# FLC100_remote_v1_2.net
KiCad netlist of a schematic drawn in EAGLE
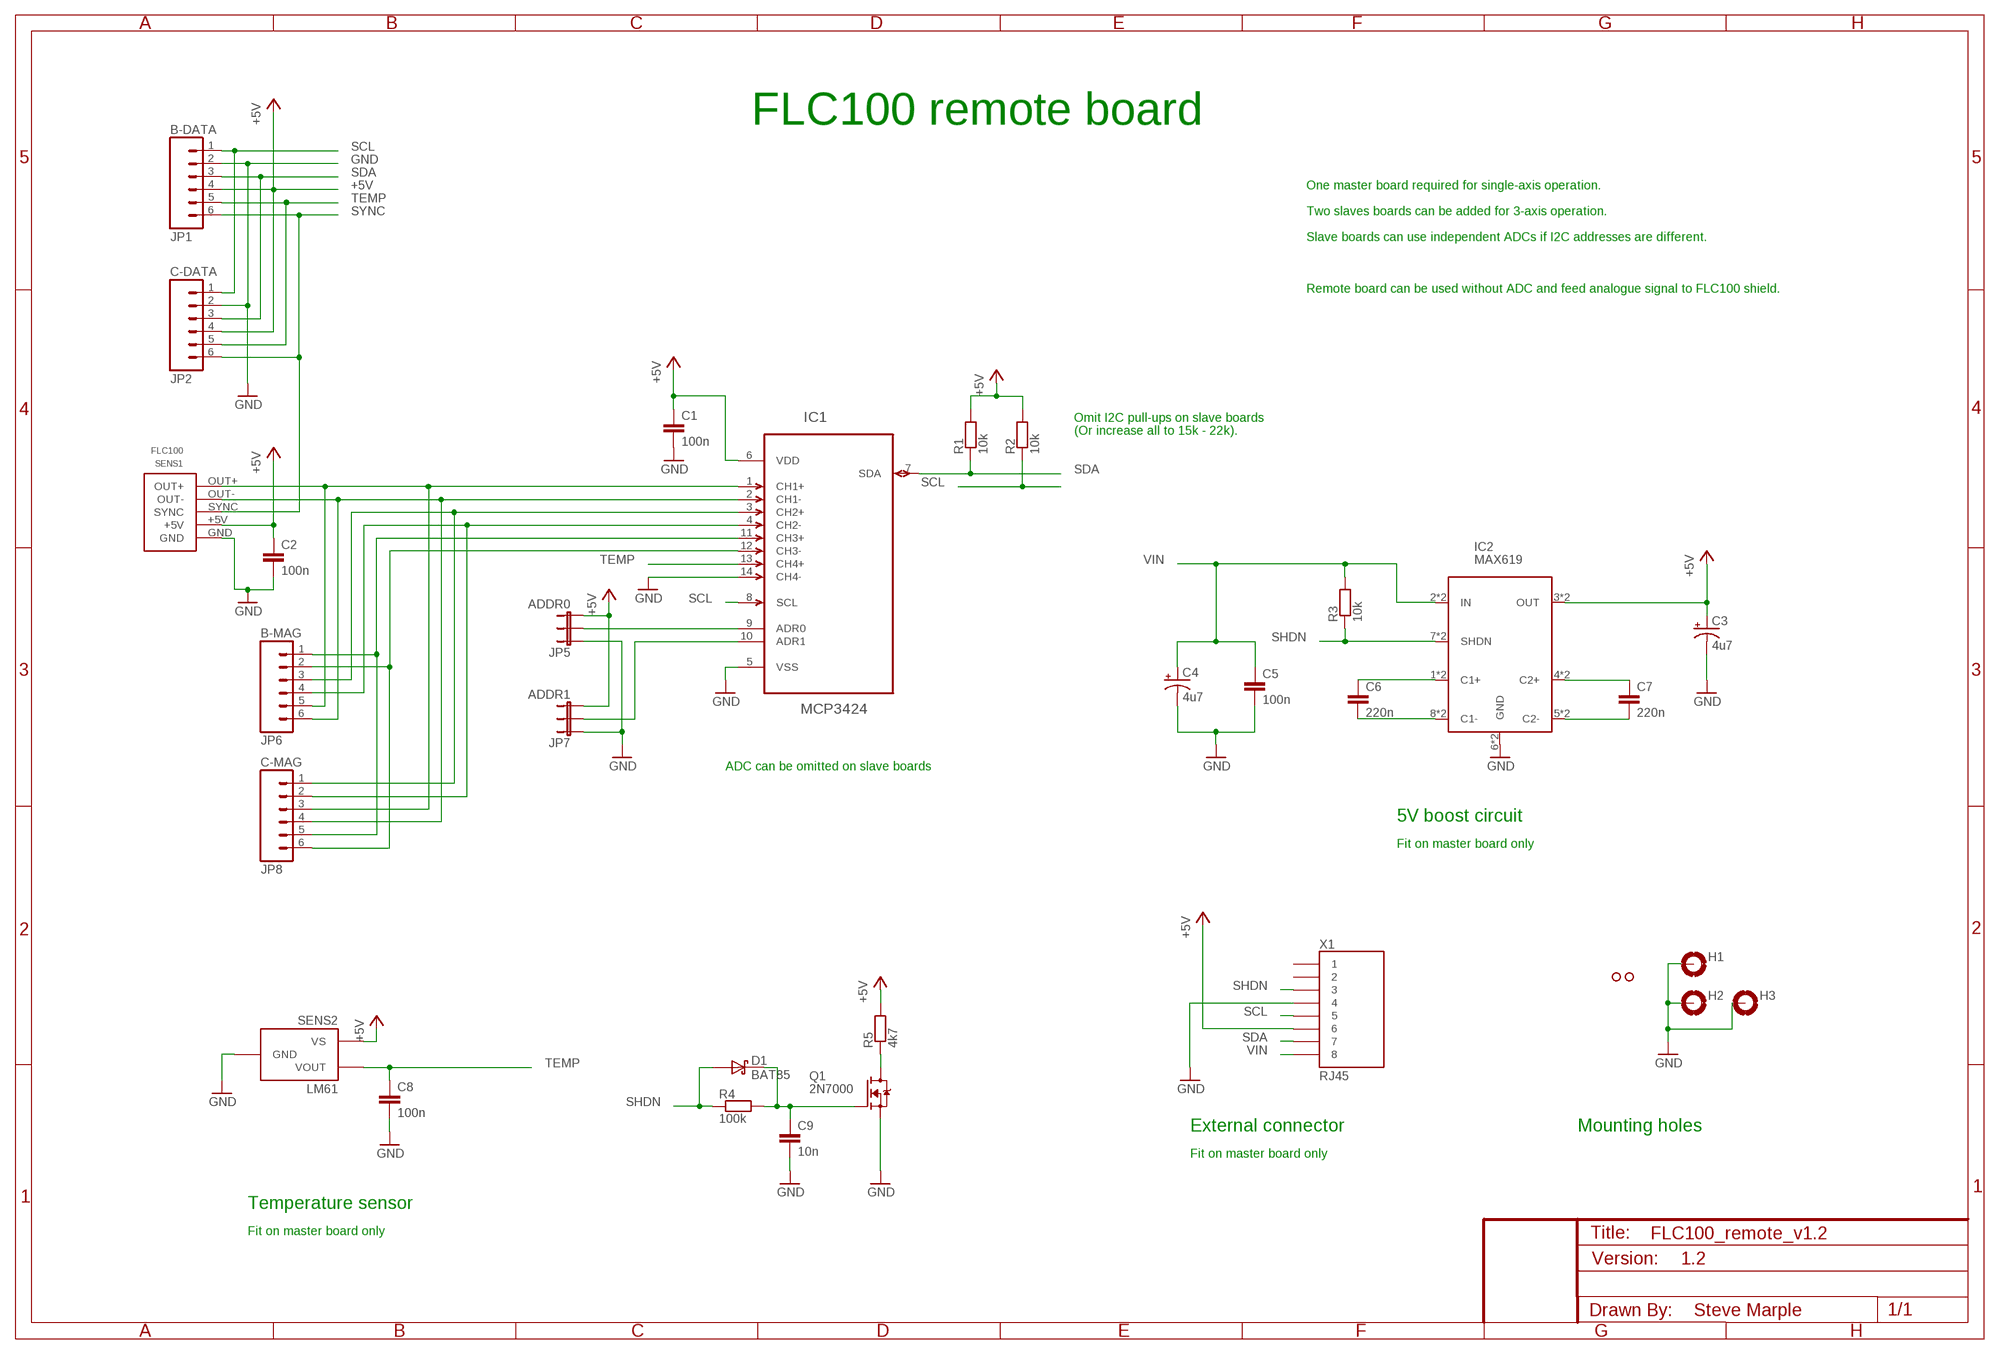
[diagram p0: schematic, sheet 1]

(export (version "E")
  (design (tool "Eeschema 10.0.6"))
  (components
    (comp (ref "C1")
      (value "100n")
      (footprint "eagle-import:CAP-PTH-SMALL")
      (libsource (lib "eagle-import") (part "CAPPTH"))
    )
    (comp (ref "C2")
      (value "100n")
      (footprint "eagle-import:CAP-PTH-SMALL")
      (libsource (lib "eagle-import") (part "CAPPTH"))
    )
    (comp (ref "C3")
      (value "4u7")
      (footprint "eagle-import:CPOL-RADIAL-10UF-25V")
      (libsource (lib "eagle-import") (part "CAP_POLPTH2"))
    )
    (comp (ref "C4")
      (value "4u7")
      (footprint "eagle-import:CPOL-RADIAL-10UF-25V")
      (libsource (lib "eagle-import") (part "CAP_POLPTH2"))
    )
    (comp (ref "C5")
      (value "100n")
      (footprint "eagle-import:CAP-PTH-SMALL")
      (libsource (lib "eagle-import") (part "CAPPTH"))
    )
    (comp (ref "C6")
      (value "220n")
      (footprint "eagle-import:CAP-PTH-5MM")
      (libsource (lib "eagle-import") (part "CAPPTH1"))
    )
    (comp (ref "C7")
      (value "220n")
      (footprint "eagle-import:CAP-PTH-5MM")
      (libsource (lib "eagle-import") (part "CAPPTH1"))
    )
    (comp (ref "C8")
      (value "100n")
      (footprint "eagle-import:CAP-PTH-SMALL")
      (libsource (lib "eagle-import") (part "CAPPTH"))
    )
    (comp (ref "C9")
      (value "10n")
      (footprint "eagle-import:CAP-PTH-SMALL")
      (libsource (lib "eagle-import") (part "CAPPTH"))
    )
    (comp (ref "D1")
      (value "BAT85")
      (footprint "eagle-import:DIODE-TH-0.4")
      (libsource (lib "eagle-import") (part "DIODE-SCHOTTKY"))
    )
    (comp (ref "H1")
      (value "MOUNT-PAD-ROUND3.0")
      (footprint "eagle-import:3,0-PAD")
      (libsource (lib "eagle-import") (part "MOUNT-PAD-ROUND3.0"))
    )
    (comp (ref "H2")
      (value "MOUNT-PAD-ROUND3.0")
      (footprint "eagle-import:3,0-PAD")
      (libsource (lib "eagle-import") (part "MOUNT-PAD-ROUND3.0"))
    )
    (comp (ref "H3")
      (value "MOUNT-PAD-ROUND3.0")
      (footprint "eagle-import:3,0-PAD")
      (libsource (lib "eagle-import") (part "MOUNT-PAD-ROUND3.0"))
    )
    (comp (ref "IC1")
      (value "MCP3424")
      (footprint "eagle-import:SO14")
      (libsource (lib "eagle-import") (part "MCP3424-E/SLSO14"))
    )
    (comp (ref "IC2")
      (value "MAX619")
      (footprint "eagle-import:DIL08-SOIC8")
      (libsource (lib "eagle-import") (part "MAX619DIL08/SOIC8"))
    )
    (comp (ref "JP1")
      (value "B-DATA")
      (footprint "eagle-import:1X06_FEMALE")
      (libsource (lib "eagle-import") (part "M06FEMALE"))
    )
    (comp (ref "JP2")
      (value "C-DATA")
      (footprint "eagle-import:1X06_FEMALE")
      (libsource (lib "eagle-import") (part "M06FEMALE"))
    )
    (comp (ref "JP5")
      (value "ADDR0")
      (footprint "eagle-import:1X03")
      (libsource (lib "eagle-import") (part "JUMPER-3PTH"))
    )
    (comp (ref "JP6")
      (value "B-MAG")
      (footprint "eagle-import:1X06_FEMALE")
      (libsource (lib "eagle-import") (part "M06FEMALE"))
    )
    (comp (ref "JP7")
      (value "ADDR1")
      (footprint "eagle-import:1X03")
      (libsource (lib "eagle-import") (part "JUMPER-3PTH"))
    )
    (comp (ref "JP8")
      (value "C-MAG")
      (footprint "eagle-import:1X06_FEMALE")
      (libsource (lib "eagle-import") (part "M06FEMALE"))
    )
    (comp (ref "Q1")
      (value "2N7000")
      (footprint "eagle-import:TO-92")
      (libsource (lib "eagle-import") (part "2N7000"))
    )
    (comp (ref "R1")
      (value "10k")
      (footprint "eagle-import:RES-AXIAL-0.4")
      (libsource (lib "eagle-import") (part "RESISTOR"))
    )
    (comp (ref "R2")
      (value "10k")
      (footprint "eagle-import:RES-AXIAL-0.4")
      (libsource (lib "eagle-import") (part "RESISTOR"))
    )
    (comp (ref "R3")
      (value "10k")
      (footprint "eagle-import:RES-AXIAL-0.4")
      (libsource (lib "eagle-import") (part "RESISTOR"))
    )
    (comp (ref "R4")
      (value "100k")
      (footprint "eagle-import:RES-AXIAL-0.4")
      (libsource (lib "eagle-import") (part "RESISTOR"))
    )
    (comp (ref "R5")
      (value "4k7")
      (footprint "eagle-import:RES-AXIAL-0.4")
      (libsource (lib "eagle-import") (part "RESISTOR"))
    )
    (comp (ref "SENS1")
      (value "FLC100")
      (footprint "eagle-import:FLC100")
      (libsource (lib "eagle-import") (part "FLC100"))
    )
    (comp (ref "SENS2")
      (value "LM61")
      (footprint "eagle-import:TO-92")
      (libsource (lib "eagle-import") (part "LM61"))
    )
    (comp (ref "U$1")
      (value "PAD")
      (footprint "eagle-import:PAD")
      (libsource (lib "eagle-import") (part "PAD"))
    )
    (comp (ref "U$2")
      (value "PAD")
      (footprint "eagle-import:PAD")
      (libsource (lib "eagle-import") (part "PAD"))
    )
    (comp (ref "X1")
      (value "RJ45")
      (footprint "eagle-import:RJ45-8")
      (libsource (lib "eagle-import") (part "RJ45-8PTH"))
    )
  )
  (nets
    (net (code "1") (name "+5V") (class "Default")
      (node (ref "C1") (pin "1") (pinfunction "1_1") (pintype "passive"))
      (node (ref "C2") (pin "1") (pinfunction "1_1") (pintype "passive"))
      (node (ref "C3") (pin "1") (pinfunction "+_1") (pintype "passive"))
      (node (ref "IC1") (pin "6") (pinfunction "VDD_6") (pintype "power_in"))
      (node (ref "IC2") (pin "3") (pinfunction "OUT_3") (pintype "power_in"))
      (node (ref "IC2") (pin "3@1") (pinfunction "OUT_3@1") (pintype "power_in"))
      (node (ref "JP1") (pin "4") (pinfunction "4_4") (pintype "passive"))
      (node (ref "JP2") (pin "4") (pinfunction "4_4") (pintype "passive"))
      (node (ref "JP5") (pin "3") (pinfunction "3_3") (pintype "passive"))
      (node (ref "JP7") (pin "3") (pinfunction "3_3") (pintype "passive"))
      (node (ref "R1") (pin "P$2") (pinfunction "2_P$2") (pintype "passive"))
      (node (ref "R2") (pin "P$2") (pinfunction "2_P$2") (pintype "passive"))
      (node (ref "R5") (pin "P$2") (pinfunction "2_P$2") (pintype "passive"))
      (node (ref "SENS1") (pin "+5V") (pinfunction "+5V_+5V") (pintype "power_in"))
      (node (ref "SENS2") (pin "1") (pinfunction "VS_1") (pintype "bidirectional"))
      (node (ref "X1") (pin "6") (pinfunction "6_6") (pintype "bidirectional"))
    )
    (net (code "2") (name "/SCL") (class "Default")
      (node (ref "IC1") (pin "8") (pinfunction "SCL_8") (pintype "input"))
      (node (ref "JP1") (pin "1") (pinfunction "1_1") (pintype "passive"))
      (node (ref "JP2") (pin "1") (pinfunction "1_1") (pintype "passive"))
      (node (ref "R2") (pin "P$1") (pinfunction "1_P$1") (pintype "passive"))
      (node (ref "X1") (pin "5") (pinfunction "5_5") (pintype "bidirectional"))
    )
    (net (code "3") (name "/SDA") (class "Default")
      (node (ref "IC1") (pin "7") (pinfunction "SDA_7") (pintype "bidirectional"))
      (node (ref "JP1") (pin "3") (pinfunction "3_3") (pintype "passive"))
      (node (ref "JP2") (pin "3") (pinfunction "3_3") (pintype "passive"))
      (node (ref "R1") (pin "P$1") (pinfunction "1_P$1") (pintype "passive"))
      (node (ref "X1") (pin "7") (pinfunction "7_7") (pintype "bidirectional"))
    )
    (net (code "4") (name "/SHDN") (class "Default")
      (node (ref "D1") (pin "A") (pinfunction "A_A") (pintype "passive"))
      (node (ref "IC2") (pin "7") (pinfunction "SHDN_7") (pintype "input"))
      (node (ref "IC2") (pin "7@1") (pinfunction "SHDN_7@1") (pintype "input"))
      (node (ref "R3") (pin "P$1") (pinfunction "1_P$1") (pintype "passive"))
      (node (ref "R4") (pin "P$1") (pinfunction "1_P$1") (pintype "passive"))
      (node (ref "X1") (pin "3") (pinfunction "3_3") (pintype "bidirectional"))
    )
    (net (code "5") (name "/SYNC") (class "Default")
      (node (ref "JP1") (pin "6") (pinfunction "6_6") (pintype "passive"))
      (node (ref "JP2") (pin "6") (pinfunction "6_6") (pintype "passive"))
      (node (ref "SENS1") (pin "SYNC") (pinfunction "SYNC_SYNC") (pintype "bidirectional"))
    )
    (net (code "6") (name "/TEMP") (class "Default")
      (node (ref "C8") (pin "1") (pinfunction "1_1") (pintype "passive"))
      (node (ref "IC1") (pin "13") (pinfunction "CH4+_13") (pintype "input"))
      (node (ref "JP1") (pin "5") (pinfunction "5_5") (pintype "passive"))
      (node (ref "JP2") (pin "5") (pinfunction "5_5") (pintype "passive"))
      (node (ref "SENS2") (pin "2") (pinfunction "VOUT_2") (pintype "bidirectional"))
    )
    (net (code "7") (name "/VIN") (class "Default")
      (node (ref "C4") (pin "1") (pinfunction "+_1") (pintype "passive"))
      (node (ref "C5") (pin "1") (pinfunction "1_1") (pintype "passive"))
      (node (ref "IC2") (pin "2") (pinfunction "IN_2") (pintype "power_in"))
      (node (ref "IC2") (pin "2@1") (pinfunction "IN_2@1") (pintype "power_in"))
      (node (ref "R3") (pin "P$2") (pinfunction "2_P$2") (pintype "passive"))
      (node (ref "X1") (pin "8") (pinfunction "8_8") (pintype "bidirectional"))
    )
    (net (code "8") (name "GND") (class "Default")
      (node (ref "C1") (pin "2") (pinfunction "2_2") (pintype "passive"))
      (node (ref "C2") (pin "2") (pinfunction "2_2") (pintype "passive"))
      (node (ref "C3") (pin "2") (pinfunction "-_2") (pintype "passive"))
      (node (ref "C4") (pin "2") (pinfunction "-_2") (pintype "passive"))
      (node (ref "C5") (pin "2") (pinfunction "2_2") (pintype "passive"))
      (node (ref "C8") (pin "2") (pinfunction "2_2") (pintype "passive"))
      (node (ref "C9") (pin "2") (pinfunction "2_2") (pintype "passive"))
      (node (ref "H1") (pin "B3,0") (pinfunction "MOUNT_B3,0") (pintype "passive"))
      (node (ref "H2") (pin "B3,0") (pinfunction "MOUNT_B3,0") (pintype "passive"))
      (node (ref "H3") (pin "B3,0") (pinfunction "MOUNT_B3,0") (pintype "passive"))
      (node (ref "IC1") (pin "14") (pinfunction "CH4-_14") (pintype "input"))
      (node (ref "IC1") (pin "5") (pinfunction "VSS_5") (pintype "power_in"))
      (node (ref "IC2") (pin "6") (pinfunction "GND_6") (pintype "power_in"))
      (node (ref "IC2") (pin "6@1") (pinfunction "GND_6@1") (pintype "power_in"))
      (node (ref "JP1") (pin "2") (pinfunction "2_2") (pintype "passive"))
      (node (ref "JP2") (pin "2") (pinfunction "2_2") (pintype "passive"))
      (node (ref "JP5") (pin "1") (pinfunction "1_1") (pintype "passive"))
      (node (ref "JP7") (pin "1") (pinfunction "1_1") (pintype "passive"))
      (node (ref "Q1") (pin "1") (pinfunction "S_1") (pintype "passive"))
      (node (ref "SENS1") (pin "GND") (pinfunction "GND_GND") (pintype "power_in"))
      (node (ref "SENS2") (pin "3") (pinfunction "GND_3") (pintype "bidirectional"))
      (node (ref "X1") (pin "4") (pinfunction "4_4") (pintype "bidirectional"))
    )
    (net (code "9") (name "Net-(C6-Pad1)") (class "Default")
      (node (ref "C6") (pin "1") (pinfunction "1_1") (pintype "passive"))
      (node (ref "IC2") (pin "1") (pinfunction "C1+_1") (pintype "bidirectional"))
      (node (ref "IC2") (pin "1@1") (pinfunction "C1+_1@1") (pintype "bidirectional"))
    )
    (net (code "10") (name "Net-(C6-Pad2)") (class "Default")
      (node (ref "C6") (pin "2") (pinfunction "2_2") (pintype "passive"))
      (node (ref "IC2") (pin "8") (pinfunction "C1-_8") (pintype "bidirectional"))
      (node (ref "IC2") (pin "8@1") (pinfunction "C1-_8@1") (pintype "bidirectional"))
    )
    (net (code "11") (name "Net-(C7-Pad1)") (class "Default")
      (node (ref "C7") (pin "1") (pinfunction "1_1") (pintype "passive"))
      (node (ref "IC2") (pin "4") (pinfunction "C2+_4") (pintype "bidirectional"))
      (node (ref "IC2") (pin "4@1") (pinfunction "C2+_4@1") (pintype "bidirectional"))
    )
    (net (code "12") (name "Net-(C7-Pad2)") (class "Default")
      (node (ref "C7") (pin "2") (pinfunction "2_2") (pintype "passive"))
      (node (ref "IC2") (pin "5") (pinfunction "C2-_5") (pintype "bidirectional"))
      (node (ref "IC2") (pin "5@1") (pinfunction "C2-_5@1") (pintype "bidirectional"))
    )
    (net (code "13") (name "Net-(IC1-ADR0)") (class "Default")
      (node (ref "IC1") (pin "9") (pinfunction "ADR0_9") (pintype "input"))
      (node (ref "JP5") (pin "2") (pinfunction "2_2") (pintype "passive"))
    )
    (net (code "14") (name "Net-(IC1-ADR1)") (class "Default")
      (node (ref "IC1") (pin "10") (pinfunction "ADR1_10") (pintype "input"))
      (node (ref "JP7") (pin "2") (pinfunction "2_2") (pintype "passive"))
    )
    (net (code "15") (name "Net-(IC1-CH1+)") (class "Default")
      (node (ref "IC1") (pin "1") (pinfunction "CH1+_1") (pintype "input"))
      (node (ref "JP6") (pin "5") (pinfunction "5_5") (pintype "passive"))
      (node (ref "JP8") (pin "3") (pinfunction "3_3") (pintype "passive"))
      (node (ref "SENS1") (pin "OUT+") (pinfunction "OUT+_OUT+") (pintype "output"))
    )
    (net (code "16") (name "Net-(IC1-CH1-)") (class "Default")
      (node (ref "IC1") (pin "2") (pinfunction "CH1-_2") (pintype "input"))
      (node (ref "JP6") (pin "6") (pinfunction "6_6") (pintype "passive"))
      (node (ref "JP8") (pin "4") (pinfunction "4_4") (pintype "passive"))
      (node (ref "SENS1") (pin "OUT-") (pinfunction "OUT-_OUT-") (pintype "output"))
    )
    (net (code "17") (name "Net-(IC1-CH2+)") (class "Default")
      (node (ref "IC1") (pin "3") (pinfunction "CH2+_3") (pintype "input"))
      (node (ref "JP6") (pin "3") (pinfunction "3_3") (pintype "passive"))
      (node (ref "JP8") (pin "1") (pinfunction "1_1") (pintype "passive"))
    )
    (net (code "18") (name "Net-(IC1-CH2-)") (class "Default")
      (node (ref "IC1") (pin "4") (pinfunction "CH2-_4") (pintype "input"))
      (node (ref "JP6") (pin "4") (pinfunction "4_4") (pintype "passive"))
      (node (ref "JP8") (pin "2") (pinfunction "2_2") (pintype "passive"))
    )
    (net (code "19") (name "Net-(IC1-CH3+)") (class "Default")
      (node (ref "IC1") (pin "11") (pinfunction "CH3+_11") (pintype "input"))
      (node (ref "JP6") (pin "1") (pinfunction "1_1") (pintype "passive"))
      (node (ref "JP8") (pin "5") (pinfunction "5_5") (pintype "passive"))
    )
    (net (code "20") (name "Net-(IC1-CH3-)") (class "Default")
      (node (ref "IC1") (pin "12") (pinfunction "CH3-_12") (pintype "input"))
      (node (ref "JP6") (pin "2") (pinfunction "2_2") (pintype "passive"))
      (node (ref "JP8") (pin "6") (pinfunction "6_6") (pintype "passive"))
    )
    (net (code "21") (name "Net-(Q1-D)") (class "Default")
      (node (ref "Q1") (pin "3") (pinfunction "D_3") (pintype "passive"))
      (node (ref "R5") (pin "P$1") (pinfunction "1_P$1") (pintype "passive"))
    )
    (net (code "22") (name "Net-(Q1-G)") (class "Default")
      (node (ref "C9") (pin "1") (pinfunction "1_1") (pintype "passive"))
      (node (ref "D1") (pin "C") (pinfunction "C_C") (pintype "passive"))
      (node (ref "Q1") (pin "2") (pinfunction "G_2") (pintype "passive"))
      (node (ref "R4") (pin "P$2") (pinfunction "2_P$2") (pintype "passive"))
    )
    (net (code "23") (name "unconnected-(U$1-Pad1)") (class "Default")
      (node (ref "U$1") (pin "1") (pinfunction "1_1") (pintype "bidirectional"))
    )
    (net (code "24") (name "unconnected-(U$2-Pad1)") (class "Default")
      (node (ref "U$2") (pin "1") (pinfunction "1_1") (pintype "bidirectional"))
    )
    (net (code "25") (name "unconnected-(X1-Pad1)") (class "Default")
      (node (ref "X1") (pin "1") (pinfunction "1_1") (pintype "bidirectional"))
    )
    (net (code "26") (name "unconnected-(X1-Pad2)") (class "Default")
      (node (ref "X1") (pin "2") (pinfunction "2_2") (pintype "bidirectional"))
    )
  )
)
